# op-synth_1_0.net
KiCad netlist of a schematic drawn in EAGLE
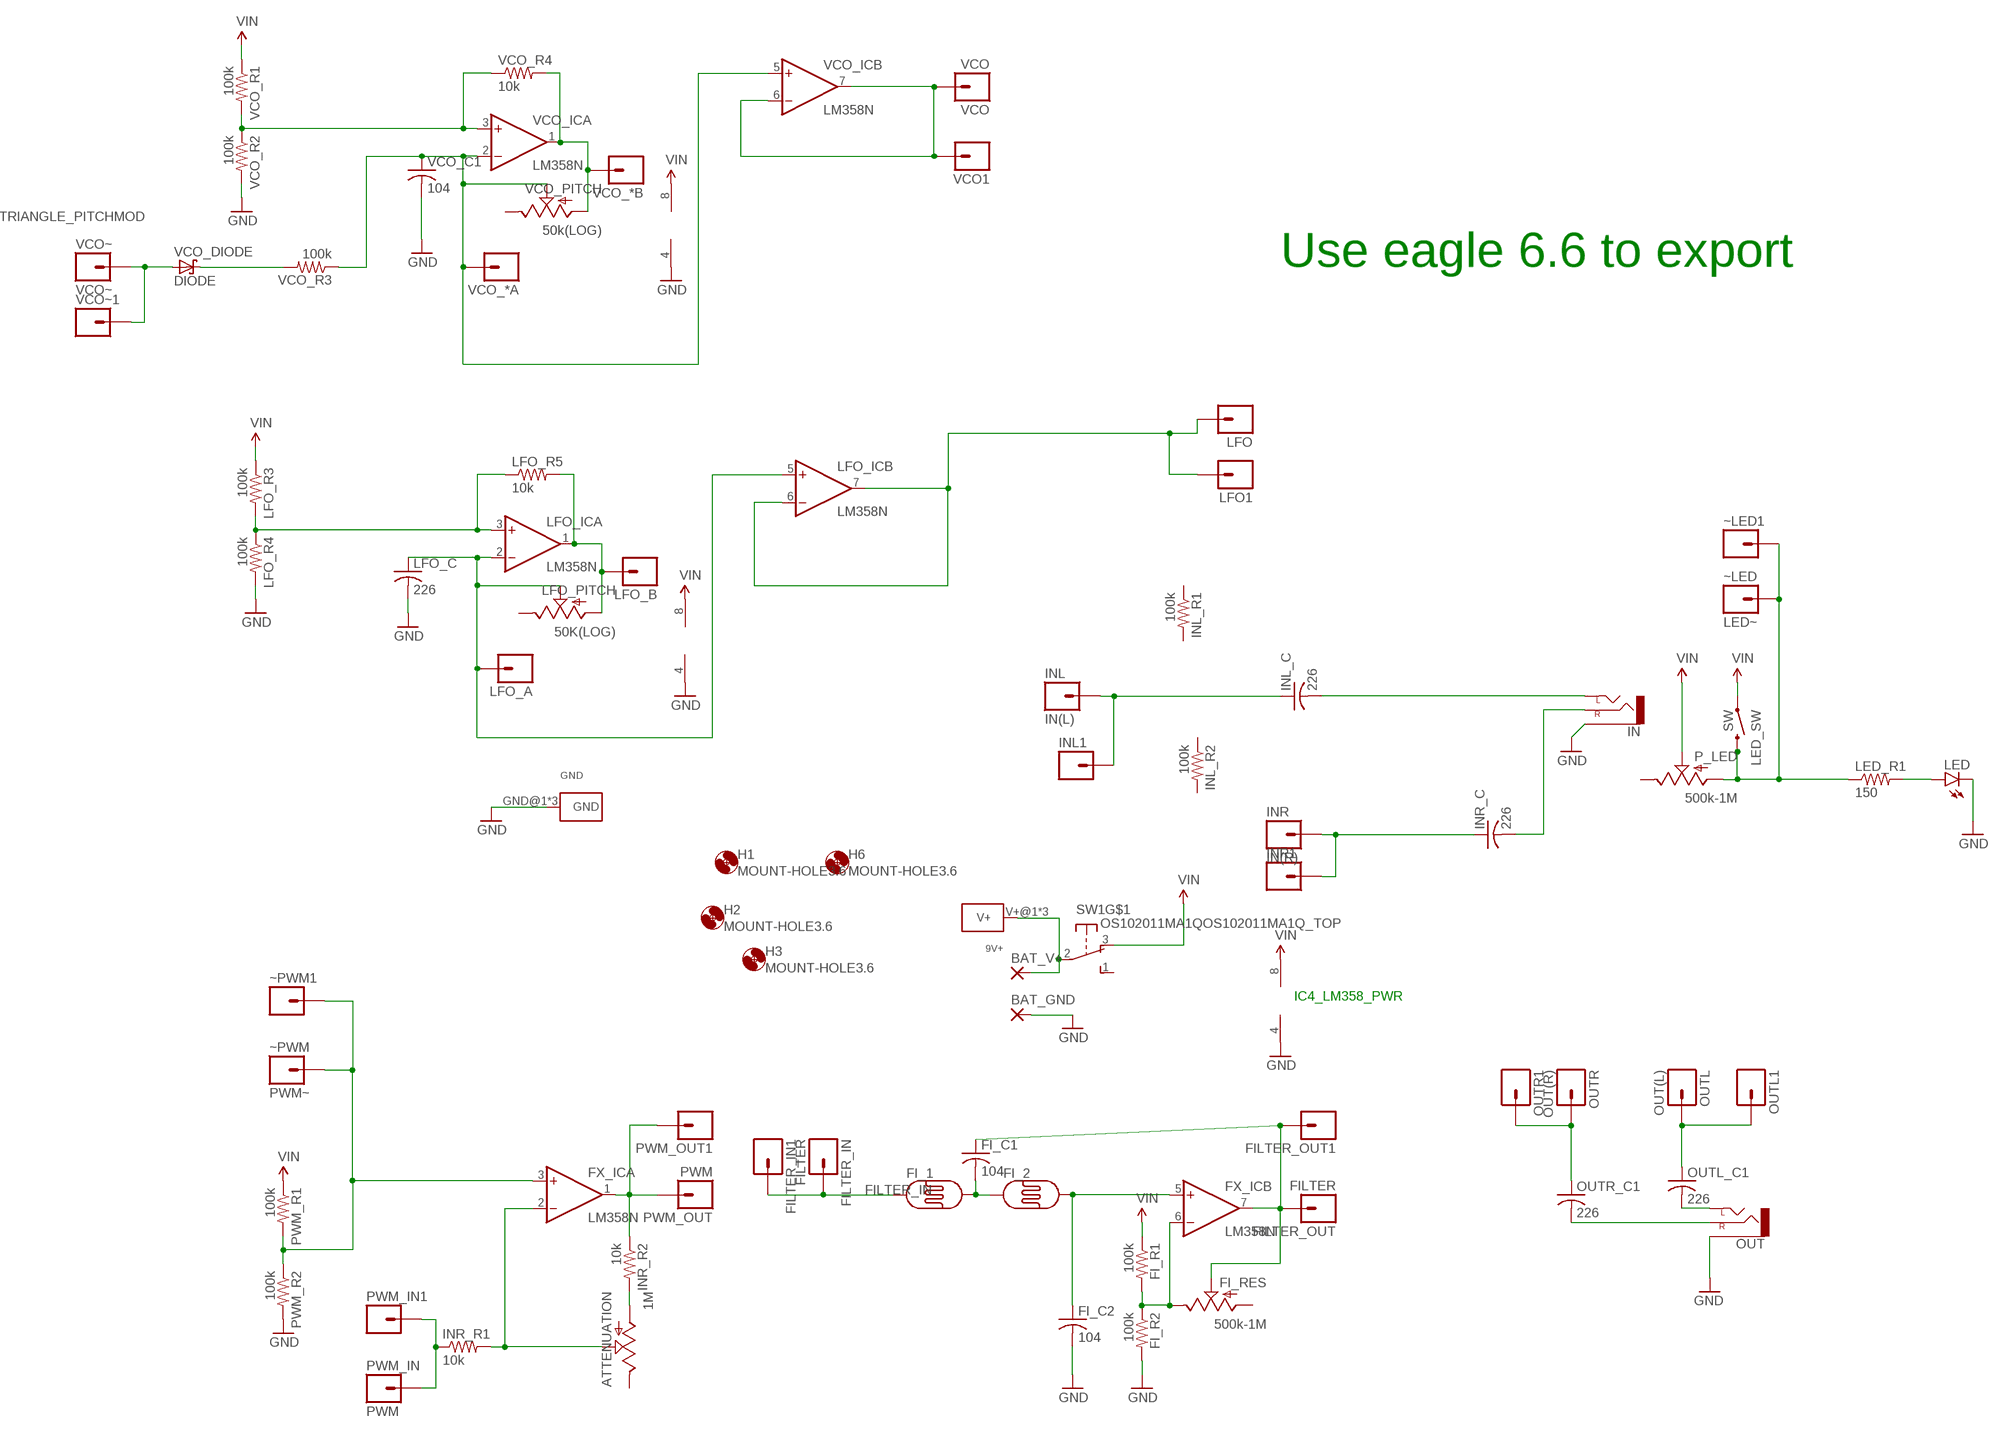
[diagram p0: schematic, sheet 1]

(export (version "E")
  (design (tool "Eeschema 10.0.6"))
  (components
    (comp (ref "9V+")
      (value "KEYSTONE-629+")
      (footprint "eagle-import:KEYSTONE_BATTAERY_TERMINAL-629+")
      (libsource (lib "eagle-import") (part "KEYSTONE-629+"))
    )
    (comp (ref "ATTENUATION")
      (value "1M")
      (footprint "eagle-import:TRIM_POT")
      (libsource (lib "eagle-import") (part "POTTRIM"))
    )
    (comp (ref "BAT_GND")
      (value "3,81/1,4")
      (footprint "eagle-import:3,81_1,4")
      (libsource (lib "eagle-import") (part "3,81/1,4"))
    )
    (comp (ref "BAT_V+")
      (value "3,81/1,4")
      (footprint "eagle-import:3,81_1,4")
      (libsource (lib "eagle-import") (part "3,81/1,4"))
    )
    (comp (ref "FILTER_IN")
      (value "FILTER")
      (footprint "eagle-import:1X01_SIDE_NAME")
      (libsource (lib "eagle-import") (part "HEADER-1X1"))
    )
    (comp (ref "FILTER_IN1")
      (value "HEADER-1X1")
      (footprint "eagle-import:1X01_SIDE_NAME")
      (libsource (lib "eagle-import") (part "HEADER-1X1"))
    )
    (comp (ref "FILTER_OUT")
      (value "FILTER")
      (footprint "eagle-import:1X01_SIDE_NAME")
      (libsource (lib "eagle-import") (part "HEADER-1X1"))
    )
    (comp (ref "FILTER_OUT1")
      (value "HEADER-1X1")
      (footprint "eagle-import:1X01_SIDE_NAME")
      (libsource (lib "eagle-import") (part "HEADER-1X1"))
    )
    (comp (ref "FI_1")
      (value "PHOTOCELLPTH")
      (footprint "eagle-import:PHOTOCELL")
      (libsource (lib "eagle-import") (part "PHOTOCELLPTH"))
    )
    (comp (ref "FI_2")
      (value "PHOTOCELLPTH")
      (footprint "eagle-import:PHOTOCELL")
      (libsource (lib "eagle-import") (part "PHOTOCELLPTH"))
    )
    (comp (ref "FI_C1")
      (value "104")
      (footprint "eagle-import:C050-024X044")
      (libsource (lib "eagle-import") (part "resistor_C-US050-024X044"))
    )
    (comp (ref "FI_C2")
      (value "104")
      (footprint "eagle-import:C050-024X044")
      (libsource (lib "eagle-import") (part "resistor_C-US050-024X044"))
    )
    (comp (ref "FI_R1")
      (value "100k")
      (footprint "eagle-import:0204_7")
      (libsource (lib "eagle-import") (part "R-US_0204/7"))
    )
    (comp (ref "FI_R2")
      (value "100k")
      (footprint "eagle-import:0204_7")
      (libsource (lib "eagle-import") (part "R-US_0204/7"))
    )
    (comp (ref "FI_RES")
      (value "500k-1M")
      (footprint "eagle-import:ALPS_POT")
      (libsource (lib "eagle-import") (part "POT"))
    )
    (comp (ref "FX_IC")
      (value "LM358N")
      (footprint "eagle-import:DIL08")
      (libsource (lib "eagle-import") (part "LM358N"))
    )
    (comp (ref "GND")
      (value "KEYSTONE-629")
      (footprint "eagle-import:KEYSTONE_AA_AAA_BATTERY_TERMINAL-629")
      (libsource (lib "eagle-import") (part "KEYSTONE-629"))
    )
    (comp (ref "H1")
      (value "MOUNT-HOLE3.6")
      (footprint "eagle-import:3,6")
      (libsource (lib "eagle-import") (part "MOUNT-HOLE3.6"))
    )
    (comp (ref "H2")
      (value "MOUNT-HOLE3.6")
      (footprint "eagle-import:3,6")
      (libsource (lib "eagle-import") (part "MOUNT-HOLE3.6"))
    )
    (comp (ref "H3")
      (value "MOUNT-HOLE3.6")
      (footprint "eagle-import:3,6")
      (libsource (lib "eagle-import") (part "MOUNT-HOLE3.6"))
    )
    (comp (ref "H6")
      (value "MOUNT-HOLE3.6")
      (footprint "eagle-import:3,6")
      (libsource (lib "eagle-import") (part "MOUNT-HOLE3.6"))
    )
    (comp (ref "IN")
      (value "AUDIO-JACKPTH")
      (footprint "eagle-import:AUDIO-JACK")
      (libsource (lib "eagle-import") (part "AUDIO-JACKPTH"))
    )
    (comp (ref "INL")
      (value "IN(L)")
      (footprint "eagle-import:1X01_SIDE_NAME")
      (libsource (lib "eagle-import") (part "HEADER-1X1"))
    )
    (comp (ref "INL1")
      (value "HEADER-1X1")
      (footprint "eagle-import:1X01_SIDE_NAME")
      (libsource (lib "eagle-import") (part "HEADER-1X1"))
    )
    (comp (ref "INL_C")
      (value "226")
      (footprint "eagle-import:C050-024X044")
      (libsource (lib "eagle-import") (part "C-US050-024X044"))
    )
    (comp (ref "INL_R1")
      (value "100k")
      (footprint "eagle-import:0204_7")
      (libsource (lib "eagle-import") (part "R-US_0204/7"))
    )
    (comp (ref "INL_R2")
      (value "100k")
      (footprint "eagle-import:0204_7")
      (libsource (lib "eagle-import") (part "R-US_0204/7"))
    )
    (comp (ref "INR")
      (value "IN(R)")
      (footprint "eagle-import:1X01_SIDE_NAME")
      (libsource (lib "eagle-import") (part "HEADER-1X1"))
    )
    (comp (ref "INR1")
      (value "HEADER-1X1")
      (footprint "eagle-import:1X01_SIDE_NAME")
      (libsource (lib "eagle-import") (part "HEADER-1X1"))
    )
    (comp (ref "INR_C")
      (value "226")
      (footprint "eagle-import:C050-024X044")
      (libsource (lib "eagle-import") (part "C-US050-024X044"))
    )
    (comp (ref "INR_R1")
      (value "10k")
      (footprint "eagle-import:0204_7")
      (libsource (lib "eagle-import") (part "R-US_0204/7"))
    )
    (comp (ref "INR_R2")
      (value "10k")
      (footprint "eagle-import:0204_7")
      (libsource (lib "eagle-import") (part "R-US_0204/7"))
    )
    (comp (ref "LED")
      (value "LED5MM")
      (footprint "eagle-import:LED5MM")
      (libsource (lib "eagle-import") (part "LED5MM"))
    )
    (comp (ref "LED_R1")
      (value "150")
      (footprint "eagle-import:0204_7")
      (libsource (lib "eagle-import") (part "R-US_0204/7"))
    )
    (comp (ref "LED_SW")
      (value "SW")
      (footprint "eagle-import:TACTILE-PTH-12MM")
      (libsource (lib "eagle-import") (part "SWITCH-MOMENTARY-212MM"))
    )
    (comp (ref "LFO")
      (value "HEADER-1X1")
      (footprint "eagle-import:1X01_SIDE_NAME")
      (libsource (lib "eagle-import") (part "HEADER-1X1"))
    )
    (comp (ref "LFO1")
      (value "HEADER-1X1")
      (footprint "eagle-import:1X01_SIDE_NAME")
      (libsource (lib "eagle-import") (part "HEADER-1X1"))
    )
    (comp (ref "LFO_A")
      (value "HEADER-1X1")
      (footprint "eagle-import:1X01_SIDE_NAME")
      (libsource (lib "eagle-import") (part "HEADER-1X1"))
    )
    (comp (ref "LFO_B")
      (value "HEADER-1X1")
      (footprint "eagle-import:1X01_SIDE_NAME")
      (libsource (lib "eagle-import") (part "HEADER-1X1"))
    )
    (comp (ref "LFO_C")
      (value "226")
      (footprint "eagle-import:C050-024X044")
      (libsource (lib "eagle-import") (part "resistor_C-US050-024X044"))
    )
    (comp (ref "LFO_IC")
      (value "LM358N")
      (footprint "eagle-import:DIL08")
      (libsource (lib "eagle-import") (part "LM358N"))
    )
    (comp (ref "LFO_PITCH")
      (value "50K(LOG)")
      (footprint "eagle-import:ALPS_POT")
      (libsource (lib "eagle-import") (part "POT"))
    )
    (comp (ref "LFO_R3")
      (value "100k")
      (footprint "eagle-import:0204_7")
      (libsource (lib "eagle-import") (part "R-US_0204/7"))
    )
    (comp (ref "LFO_R4")
      (value "100k")
      (footprint "eagle-import:0204_7")
      (libsource (lib "eagle-import") (part "R-US_0204/7"))
    )
    (comp (ref "LFO_R5")
      (value "10k")
      (footprint "eagle-import:0204_7")
      (libsource (lib "eagle-import") (part "R-US_0204/7"))
    )
    (comp (ref "OUT")
      (value "AUDIO-JACKPTH")
      (footprint "eagle-import:AUDIO-JACK")
      (libsource (lib "eagle-import") (part "AUDIO-JACKPTH"))
    )
    (comp (ref "OUTL")
      (value "OUT(L)")
      (footprint "eagle-import:1X01_SIDE_NAME")
      (libsource (lib "eagle-import") (part "HEADER-1X1"))
    )
    (comp (ref "OUTL1")
      (value "HEADER-1X1")
      (footprint "eagle-import:1X01_SIDE_NAME")
      (libsource (lib "eagle-import") (part "HEADER-1X1"))
    )
    (comp (ref "OUTL_C1")
      (value "226")
      (footprint "eagle-import:C050-024X044")
      (libsource (lib "eagle-import") (part "C-US050-024X044"))
    )
    (comp (ref "OUTR")
      (value "OUT(R)")
      (footprint "eagle-import:1X01_SIDE_NAME")
      (libsource (lib "eagle-import") (part "HEADER-1X1"))
    )
    (comp (ref "OUTR1")
      (value "HEADER-1X1")
      (footprint "eagle-import:1X01_SIDE_NAME")
      (libsource (lib "eagle-import") (part "HEADER-1X1"))
    )
    (comp (ref "OUTR_C1")
      (value "226")
      (footprint "eagle-import:C050-024X044")
      (libsource (lib "eagle-import") (part "C-US050-024X044"))
    )
    (comp (ref "PWM_IN")
      (value "PWM")
      (footprint "eagle-import:1X01_SIDE_NAME")
      (libsource (lib "eagle-import") (part "HEADER-1X1"))
    )
    (comp (ref "PWM_IN1")
      (value "HEADER-1X1")
      (footprint "eagle-import:1X01_SIDE_NAME")
      (libsource (lib "eagle-import") (part "HEADER-1X1"))
    )
    (comp (ref "PWM_OUT")
      (value "PWM")
      (footprint "eagle-import:1X01_SIDE_NAME")
      (libsource (lib "eagle-import") (part "HEADER-1X1"))
    )
    (comp (ref "PWM_OUT1")
      (value "HEADER-1X1")
      (footprint "eagle-import:1X01_SIDE_NAME")
      (libsource (lib "eagle-import") (part "HEADER-1X1"))
    )
    (comp (ref "PWM_R1")
      (value "100k")
      (footprint "eagle-import:0204_7")
      (libsource (lib "eagle-import") (part "R-US_0204/7"))
    )
    (comp (ref "PWM_R2")
      (value "100k")
      (footprint "eagle-import:0204_7")
      (libsource (lib "eagle-import") (part "R-US_0204/7"))
    )
    (comp (ref "P_LED")
      (value "500k-1M")
      (footprint "eagle-import:ALPS_POT")
      (libsource (lib "eagle-import") (part "POT"))
    )
    (comp (ref "SW1")
      (value "OS102011MA1QOS102011MA1Q_TOP")
      (footprint "eagle-import:OS102011MA1Q")
      (libsource (lib "eagle-import") (part "OS102011MA1QOS102011MA1Q_TOP"))
    )
    (comp (ref "VCO")
      (value "VCO")
      (footprint "eagle-import:1X01_SIDE_NAME")
      (libsource (lib "eagle-import") (part "HEADER-1X1"))
    )
    (comp (ref "VCO1")
      (value "HEADER-1X1")
      (footprint "eagle-import:1X01_SIDE_NAME")
      (libsource (lib "eagle-import") (part "HEADER-1X1"))
    )
    (comp (ref "VCO_*A")
      (value "HEADER-1X1")
      (footprint "eagle-import:1X01_SIDE_NAME")
      (libsource (lib "eagle-import") (part "HEADER-1X1"))
    )
    (comp (ref "VCO_*B")
      (value "HEADER-1X1")
      (footprint "eagle-import:1X01_SIDE_NAME")
      (libsource (lib "eagle-import") (part "HEADER-1X1"))
    )
    (comp (ref "VCO_C1")
      (value "104")
      (footprint "eagle-import:C050-024X044")
      (libsource (lib "eagle-import") (part "C-US050-024X044"))
    )
    (comp (ref "VCO_DIODE")
      (value "DIODE")
      (footprint "eagle-import:DO41-7")
      (libsource (lib "eagle-import") (part "SCHOTTKY-DIODEDO41-7"))
    )
    (comp (ref "VCO_IC")
      (value "LM358N")
      (footprint "eagle-import:DIL08")
      (libsource (lib "eagle-import") (part "LM358N"))
    )
    (comp (ref "VCO_PITCH")
      (value "50k(LOG)")
      (footprint "eagle-import:ALPS_POT")
      (libsource (lib "eagle-import") (part "POT"))
    )
    (comp (ref "VCO_R1")
      (value "100k")
      (footprint "eagle-import:0204_7")
      (libsource (lib "eagle-import") (part "R-US_0204/7"))
    )
    (comp (ref "VCO_R2")
      (value "100k")
      (footprint "eagle-import:0204_7")
      (libsource (lib "eagle-import") (part "R-US_0204/7"))
    )
    (comp (ref "VCO_R3")
      (value "100k")
      (footprint "eagle-import:0204_7")
      (libsource (lib "eagle-import") (part "R-US_0204/7"))
    )
    (comp (ref "VCO_R4")
      (value "10k")
      (footprint "eagle-import:0204_7")
      (libsource (lib "eagle-import") (part "R-US_0204/7"))
    )
    (comp (ref "VCO~")
      (value "VCO~")
      (footprint "eagle-import:1X01_SIDE_NAME")
      (libsource (lib "eagle-import") (part "HEADER-1X1"))
    )
    (comp (ref "VCO~1")
      (value "HEADER-1X1")
      (footprint "eagle-import:1X01_SIDE_NAME")
      (libsource (lib "eagle-import") (part "HEADER-1X1"))
    )
    (comp (ref "~LED")
      (value "LED~")
      (footprint "eagle-import:1X01_SIDE_NAME")
      (libsource (lib "eagle-import") (part "HEADER-1X1"))
    )
    (comp (ref "~LED1")
      (value "HEADER-1X1")
      (footprint "eagle-import:1X01_SIDE_NAME")
      (libsource (lib "eagle-import") (part "HEADER-1X1"))
    )
    (comp (ref "~PWM")
      (value "PWM~")
      (footprint "eagle-import:1X01_SIDE_NAME")
      (libsource (lib "eagle-import") (part "HEADER-1X1"))
    )
    (comp (ref "~PWM1")
      (value "HEADER-1X1")
      (footprint "eagle-import:1X01_SIDE_NAME")
      (libsource (lib "eagle-import") (part "HEADER-1X1"))
    )
  )
  (nets
    (net (code "1") (name "/FILTER_IN") (class "Default")
      (node (ref "FILTER_IN") (pin "1") (pinfunction "1_1") (pintype "passive"))
      (node (ref "FILTER_IN1") (pin "1") (pinfunction "1_1") (pintype "passive"))
      (node (ref "FI_1") (pin "1") (pinfunction "P$1_1") (pintype "bidirectional"))
    )
    (net (code "2") (name "/TRIANGLE_PITCHMOD") (class "Default")
      (node (ref "VCO_DIODE") (pin "A") (pinfunction "A_A") (pintype "passive"))
      (node (ref "VCO~") (pin "1") (pinfunction "1_1") (pintype "passive"))
      (node (ref "VCO~1") (pin "1") (pinfunction "1_1") (pintype "passive"))
    )
    (net (code "3") (name "GND") (class "Default")
      (node (ref "BAT_GND") (pin "1") (pinfunction "P_1") (pintype "passive"))
      (node (ref "FI_C2") (pin "2") (pinfunction "2_2") (pintype "passive"))
      (node (ref "FI_R2") (pin "2") (pinfunction "2_2") (pintype "passive"))
      (node (ref "FX_IC") (pin "4") (pinfunction "V-_4") (pintype "power_in"))
      (node (ref "GND") (pin "GND@1") (pinfunction "GND_GND@1") (pintype "power_in"))
      (node (ref "GND") (pin "GND@2") (pinfunction "GND_GND@2") (pintype "power_in"))
      (node (ref "GND") (pin "GND@3") (pinfunction "GND_GND@3") (pintype "power_in"))
      (node (ref "IN") (pin "SLEEVE") (pinfunction "SLEEVE_SLEEVE") (pintype "bidirectional"))
      (node (ref "LED") (pin "K") (pinfunction "C_K") (pintype "passive"))
      (node (ref "LFO_C") (pin "2") (pinfunction "2_2") (pintype "passive"))
      (node (ref "LFO_IC") (pin "4") (pinfunction "V-_4") (pintype "power_in"))
      (node (ref "LFO_R4") (pin "2") (pinfunction "2_2") (pintype "passive"))
      (node (ref "OUT") (pin "SLEEVE") (pinfunction "SLEEVE_SLEEVE") (pintype "bidirectional"))
      (node (ref "PWM_R2") (pin "2") (pinfunction "2_2") (pintype "passive"))
      (node (ref "VCO_C1") (pin "2") (pinfunction "2_2") (pintype "passive"))
      (node (ref "VCO_IC") (pin "4") (pinfunction "V-_4") (pintype "power_in"))
      (node (ref "VCO_R2") (pin "2") (pinfunction "2_2") (pintype "passive"))
    )
    (net (code "4") (name "Net-(ATTENUATION-A)") (class "Default")
      (node (ref "ATTENUATION") (pin "3") (pinfunction "A_3") (pintype "passive"))
      (node (ref "INR_R2") (pin "2") (pinfunction "2_2") (pintype "passive"))
    )
    (net (code "5") (name "Net-(ATTENUATION-S)") (class "Default")
      (node (ref "ATTENUATION") (pin "1") (pinfunction "S_1") (pintype "passive"))
      (node (ref "FX_IC") (pin "2") (pinfunction "-IN_2") (pintype "input"))
      (node (ref "INR_R1") (pin "2") (pinfunction "2_2") (pintype "passive"))
    )
    (net (code "6") (name "Net-(BAT_V+-P)") (class "Default")
      (node (ref "9V+") (pin "V+@1") (pinfunction "V+_V+@1") (pintype "power_in"))
      (node (ref "9V+") (pin "V+@2") (pinfunction "V+_V+@2") (pintype "power_in"))
      (node (ref "9V+") (pin "V+@3") (pinfunction "V+_V+@3") (pintype "power_in"))
      (node (ref "BAT_V+") (pin "1") (pinfunction "P_1") (pintype "passive"))
      (node (ref "SW1") (pin "2") (pinfunction "P_2") (pintype "passive"))
    )
    (net (code "7") (name "Net-(FI_1-P$2)") (class "Default")
      (node (ref "FI_1") (pin "2") (pinfunction "P$2_2") (pintype "bidirectional"))
      (node (ref "FI_2") (pin "1") (pinfunction "P$1_1") (pintype "bidirectional"))
      (node (ref "FI_C1") (pin "2") (pinfunction "2_2") (pintype "passive"))
    )
    (net (code "8") (name "Net-(FI_2-P$2)") (class "Default")
      (node (ref "FI_2") (pin "2") (pinfunction "P$2_2") (pintype "bidirectional"))
      (node (ref "FI_C2") (pin "1") (pinfunction "1_1") (pintype "passive"))
      (node (ref "FX_IC") (pin "5") (pinfunction "+IN_5") (pintype "input"))
    )
    (net (code "9") (name "Net-(FI_RES-E)") (class "Default")
      (node (ref "FI_R1") (pin "2") (pinfunction "2_2") (pintype "passive"))
      (node (ref "FI_R2") (pin "1") (pinfunction "1_1") (pintype "passive"))
      (node (ref "FI_RES") (pin "P$1") (pinfunction "E_P$1") (pintype "passive"))
      (node (ref "FX_IC") (pin "6") (pinfunction "-IN_6") (pintype "input"))
    )
    (net (code "10") (name "Net-(FI_RES-S)") (class "Default")
      (node (ref "FILTER_OUT") (pin "1") (pinfunction "1_1") (pintype "passive"))
      (node (ref "FILTER_OUT1") (pin "1") (pinfunction "1_1") (pintype "passive"))
      (node (ref "FI_C1") (pin "1") (pinfunction "1_1") (pintype "passive"))
      (node (ref "FI_RES") (pin "P$2") (pinfunction "S_P$2") (pintype "passive"))
      (node (ref "FX_IC") (pin "7") (pinfunction "OUT_7") (pintype "output"))
    )
    (net (code "11") (name "Net-(FX_ICA-+IN)") (class "Default")
      (node (ref "FX_IC") (pin "3") (pinfunction "+IN_3") (pintype "input"))
      (node (ref "PWM_R1") (pin "2") (pinfunction "2_2") (pintype "passive"))
      (node (ref "PWM_R2") (pin "1") (pinfunction "1_1") (pintype "passive"))
      (node (ref "~PWM") (pin "1") (pinfunction "1_1") (pintype "passive"))
      (node (ref "~PWM1") (pin "1") (pinfunction "1_1") (pintype "passive"))
    )
    (net (code "12") (name "Net-(FX_ICA-OUT)") (class "Default")
      (node (ref "FX_IC") (pin "1") (pinfunction "OUT_1") (pintype "output"))
      (node (ref "INR_R2") (pin "1") (pinfunction "1_1") (pintype "passive"))
      (node (ref "PWM_OUT") (pin "1") (pinfunction "1_1") (pintype "passive"))
      (node (ref "PWM_OUT1") (pin "1") (pinfunction "1_1") (pintype "passive"))
    )
    (net (code "13") (name "Net-(IN-LEFT)") (class "Default")
      (node (ref "IN") (pin "TIP") (pinfunction "LEFT_TIP") (pintype "bidirectional"))
      (node (ref "INL_C") (pin "2") (pinfunction "2_2") (pintype "passive"))
    )
    (net (code "14") (name "Net-(IN-RIGHT)") (class "Default")
      (node (ref "IN") (pin "RING") (pinfunction "RIGHT_RING") (pintype "bidirectional"))
      (node (ref "INR_C") (pin "2") (pinfunction "2_2") (pintype "passive"))
    )
    (net (code "15") (name "Net-(INL-Pad1)") (class "Default")
      (node (ref "INL") (pin "1") (pinfunction "1_1") (pintype "passive"))
      (node (ref "INL1") (pin "1") (pinfunction "1_1") (pintype "passive"))
      (node (ref "INL_C") (pin "1") (pinfunction "1_1") (pintype "passive"))
    )
    (net (code "16") (name "Net-(INR-Pad1)") (class "Default")
      (node (ref "INR") (pin "1") (pinfunction "1_1") (pintype "passive"))
      (node (ref "INR1") (pin "1") (pinfunction "1_1") (pintype "passive"))
      (node (ref "INR_C") (pin "1") (pinfunction "1_1") (pintype "passive"))
    )
    (net (code "17") (name "Net-(INR_R1-Pad1)") (class "Default")
      (node (ref "INR_R1") (pin "1") (pinfunction "1_1") (pintype "passive"))
      (node (ref "PWM_IN") (pin "1") (pinfunction "1_1") (pintype "passive"))
      (node (ref "PWM_IN1") (pin "1") (pinfunction "1_1") (pintype "passive"))
    )
    (net (code "18") (name "Net-(LED-PadA)") (class "Default")
      (node (ref "LED") (pin "A") (pinfunction "A_A") (pintype "passive"))
      (node (ref "LED_R1") (pin "2") (pinfunction "2_2") (pintype "passive"))
    )
    (net (code "19") (name "Net-(LED_SW-2)") (class "Default")
      (node (ref "LED_R1") (pin "1") (pinfunction "1_1") (pintype "passive"))
      (node (ref "LED_SW") (pin "3") (pinfunction "2_3") (pintype "passive"))
      (node (ref "P_LED") (pin "P$3") (pinfunction "A_P$3") (pintype "passive"))
      (node (ref "~LED") (pin "1") (pinfunction "1_1") (pintype "passive"))
      (node (ref "~LED1") (pin "1") (pinfunction "1_1") (pintype "passive"))
    )
    (net (code "20") (name "Net-(LFO_ICA-+IN)") (class "Default")
      (node (ref "LFO_IC") (pin "3") (pinfunction "+IN_3") (pintype "input"))
      (node (ref "LFO_R3") (pin "2") (pinfunction "2_2") (pintype "passive"))
      (node (ref "LFO_R4") (pin "1") (pinfunction "1_1") (pintype "passive"))
      (node (ref "LFO_R5") (pin "1") (pinfunction "1_1") (pintype "passive"))
    )
    (net (code "21") (name "Net-(LFO_ICA--IN)") (class "Default")
      (node (ref "LFO_A") (pin "1") (pinfunction "1_1") (pintype "passive"))
      (node (ref "LFO_C") (pin "1") (pinfunction "1_1") (pintype "passive"))
      (node (ref "LFO_IC") (pin "2") (pinfunction "-IN_2") (pintype "input"))
      (node (ref "LFO_IC") (pin "5") (pinfunction "+IN_5") (pintype "input"))
      (node (ref "LFO_PITCH") (pin "P$2") (pinfunction "S_P$2") (pintype "passive"))
    )
    (net (code "22") (name "Net-(LFO_ICA-OUT)") (class "Default")
      (node (ref "LFO_B") (pin "1") (pinfunction "1_1") (pintype "passive"))
      (node (ref "LFO_IC") (pin "1") (pinfunction "OUT_1") (pintype "output"))
      (node (ref "LFO_PITCH") (pin "P$3") (pinfunction "A_P$3") (pintype "passive"))
      (node (ref "LFO_R5") (pin "2") (pinfunction "2_2") (pintype "passive"))
    )
    (net (code "23") (name "Net-(LFO_ICB--IN)") (class "Default")
      (node (ref "LFO") (pin "1") (pinfunction "1_1") (pintype "passive"))
      (node (ref "LFO1") (pin "1") (pinfunction "1_1") (pintype "passive"))
      (node (ref "LFO_IC") (pin "6") (pinfunction "-IN_6") (pintype "input"))
      (node (ref "LFO_IC") (pin "7") (pinfunction "OUT_7") (pintype "output"))
    )
    (net (code "24") (name "Net-(OUT-LEFT)") (class "Default")
      (node (ref "OUT") (pin "TIP") (pinfunction "LEFT_TIP") (pintype "bidirectional"))
      (node (ref "OUTL_C1") (pin "2") (pinfunction "2_2") (pintype "passive"))
    )
    (net (code "25") (name "Net-(OUT-RIGHT)") (class "Default")
      (node (ref "OUT") (pin "RING") (pinfunction "RIGHT_RING") (pintype "bidirectional"))
      (node (ref "OUTR_C1") (pin "2") (pinfunction "2_2") (pintype "passive"))
    )
    (net (code "26") (name "Net-(OUTL-Pad1)") (class "Default")
      (node (ref "OUTL") (pin "1") (pinfunction "1_1") (pintype "passive"))
      (node (ref "OUTL1") (pin "1") (pinfunction "1_1") (pintype "passive"))
      (node (ref "OUTL_C1") (pin "1") (pinfunction "1_1") (pintype "passive"))
    )
    (net (code "27") (name "Net-(OUTR-Pad1)") (class "Default")
      (node (ref "OUTR") (pin "1") (pinfunction "1_1") (pintype "passive"))
      (node (ref "OUTR1") (pin "1") (pinfunction "1_1") (pintype "passive"))
      (node (ref "OUTR_C1") (pin "1") (pinfunction "1_1") (pintype "passive"))
    )
    (net (code "28") (name "Net-(VCO_DIODE-PadC)") (class "Default")
      (node (ref "VCO_DIODE") (pin "C") (pinfunction "C_C") (pintype "passive"))
      (node (ref "VCO_R3") (pin "2") (pinfunction "2_2") (pintype "passive"))
    )
    (net (code "29") (name "Net-(VCO_ICA-+IN)") (class "Default")
      (node (ref "VCO_IC") (pin "3") (pinfunction "+IN_3") (pintype "input"))
      (node (ref "VCO_R1") (pin "2") (pinfunction "2_2") (pintype "passive"))
      (node (ref "VCO_R2") (pin "1") (pinfunction "1_1") (pintype "passive"))
      (node (ref "VCO_R4") (pin "1") (pinfunction "1_1") (pintype "passive"))
    )
    (net (code "30") (name "Net-(VCO_ICA--IN)") (class "Default")
      (node (ref "VCO_*A") (pin "1") (pinfunction "1_1") (pintype "passive"))
      (node (ref "VCO_C1") (pin "1") (pinfunction "1_1") (pintype "passive"))
      (node (ref "VCO_IC") (pin "2") (pinfunction "-IN_2") (pintype "input"))
      (node (ref "VCO_IC") (pin "5") (pinfunction "+IN_5") (pintype "input"))
      (node (ref "VCO_PITCH") (pin "P$2") (pinfunction "S_P$2") (pintype "passive"))
      (node (ref "VCO_R3") (pin "1") (pinfunction "1_1") (pintype "passive"))
    )
    (net (code "31") (name "Net-(VCO_ICA-OUT)") (class "Default")
      (node (ref "VCO_*B") (pin "1") (pinfunction "1_1") (pintype "passive"))
      (node (ref "VCO_IC") (pin "1") (pinfunction "OUT_1") (pintype "output"))
      (node (ref "VCO_PITCH") (pin "P$3") (pinfunction "A_P$3") (pintype "passive"))
      (node (ref "VCO_R4") (pin "2") (pinfunction "2_2") (pintype "passive"))
    )
    (net (code "32") (name "Net-(VCO_ICB--IN)") (class "Default")
      (node (ref "VCO") (pin "1") (pinfunction "1_1") (pintype "passive"))
      (node (ref "VCO1") (pin "1") (pinfunction "1_1") (pintype "passive"))
      (node (ref "VCO_IC") (pin "6") (pinfunction "-IN_6") (pintype "input"))
      (node (ref "VCO_IC") (pin "7") (pinfunction "OUT_7") (pintype "output"))
    )
    (net (code "33") (name "VIN") (class "Default")
      (node (ref "FI_R1") (pin "1") (pinfunction "1_1") (pintype "passive"))
      (node (ref "FX_IC") (pin "8") (pinfunction "V+_8") (pintype "power_in"))
      (node (ref "LED_SW") (pin "1") (pinfunction "1_1") (pintype "passive"))
      (node (ref "LFO_IC") (pin "8") (pinfunction "V+_8") (pintype "power_in"))
      (node (ref "LFO_R3") (pin "1") (pinfunction "1_1") (pintype "passive"))
      (node (ref "PWM_R1") (pin "1") (pinfunction "1_1") (pintype "passive"))
      (node (ref "P_LED") (pin "P$2") (pinfunction "S_P$2") (pintype "passive"))
      (node (ref "SW1") (pin "3") (pinfunction "O_3") (pintype "passive"))
      (node (ref "VCO_IC") (pin "8") (pinfunction "V+_8") (pintype "power_in"))
      (node (ref "VCO_R1") (pin "1") (pinfunction "1_1") (pintype "passive"))
    )
    (net (code "34") (name "unconnected-(ATTENUATION-E-Pad2)") (class "Default")
      (node (ref "ATTENUATION") (pin "2") (pinfunction "E_2") (pintype "passive"))
    )
    (net (code "35") (name "unconnected-(FI_RES-A-PadP$3)") (class "Default")
      (node (ref "FI_RES") (pin "P$3") (pinfunction "A_P$3") (pintype "passive"))
    )
    (net (code "36") (name "unconnected-(INL_R1-Pad1)") (class "Default")
      (node (ref "INL_R1") (pin "1") (pinfunction "1_1") (pintype "passive"))
    )
    (net (code "37") (name "unconnected-(INL_R1-Pad2)") (class "Default")
      (node (ref "INL_R1") (pin "2") (pinfunction "2_2") (pintype "passive"))
    )
    (net (code "38") (name "unconnected-(INL_R2-Pad1)") (class "Default")
      (node (ref "INL_R2") (pin "1") (pinfunction "1_1") (pintype "passive"))
    )
    (net (code "39") (name "unconnected-(INL_R2-Pad2)") (class "Default")
      (node (ref "INL_R2") (pin "2") (pinfunction "2_2") (pintype "passive"))
    )
    (net (code "40") (name "unconnected-(LFO_PITCH-E-PadP$1)") (class "Default")
      (node (ref "LFO_PITCH") (pin "P$1") (pinfunction "E_P$1") (pintype "passive"))
    )
    (net (code "41") (name "unconnected-(P_LED-E-PadP$1)") (class "Default")
      (node (ref "P_LED") (pin "P$1") (pinfunction "E_P$1") (pintype "passive"))
    )
    (net (code "42") (name "unconnected-(SW1A-S-Pad1)") (class "Default")
      (node (ref "SW1") (pin "1") (pinfunction "S_1") (pintype "passive"))
    )
    (net (code "43") (name "unconnected-(VCO_PITCH-E-PadP$1)") (class "Default")
      (node (ref "VCO_PITCH") (pin "P$1") (pinfunction "E_P$1") (pintype "passive"))
    )
  )
)
